# Motor_Control.net
KiCad netlist of a schematic drawn in Altium Designer
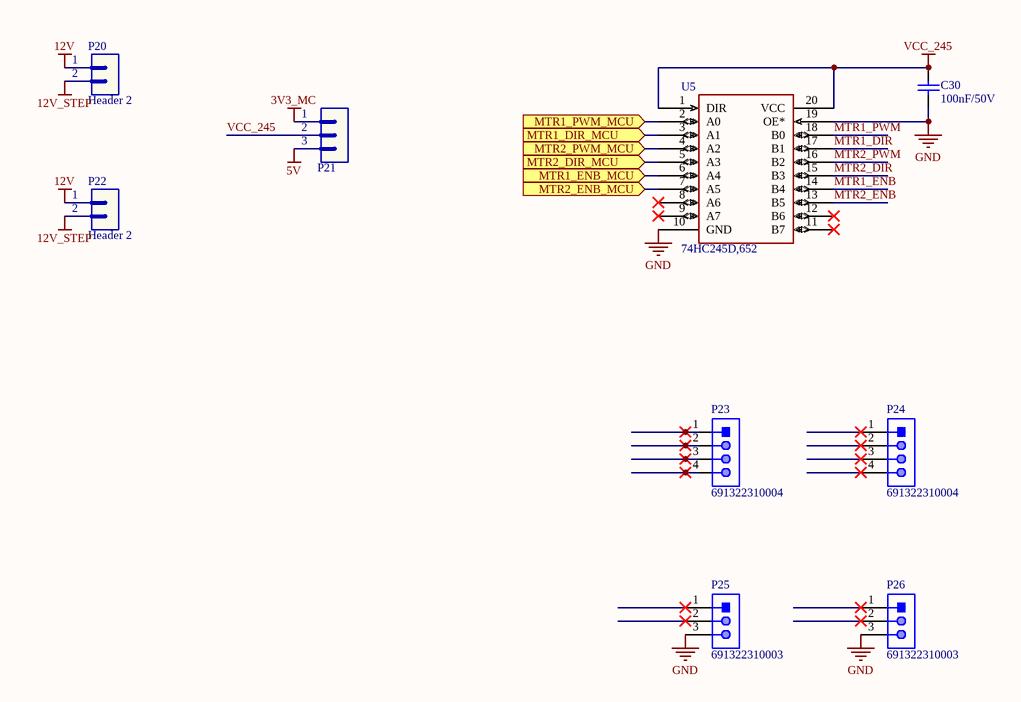
[diagram p0: Motor Control.SchDoc]

(export (version "E")
  (design (tool "Eeschema 10.0.6"))
  (components
    (comp (ref "C30")
      (value "100nF/50V")
      (footprint "CAP-SM-0805")
      (description "CAP CER 0.1UF 50V Y5V 0805")
      (fields
        (field (name "MANUFACTURER") "Samsung Electro-Mechanics")
        (field (name "MANUFACTURER PART NUMBER") "CL21F104ZBCNNNC")
      )
      (libsource (lib "Capacitor") (part "Cap-100nF-50V-0805"))
    )
    (comp (ref "P20")
      (value "Header 2")
      (footprint "JP2")
      (description "Header, 2-Pin")
      (fields (field (name "PUBLISHER") "Altium Limited"))
      (libsource (lib "PIF_C16_lib") (part "Header 2"))
    )
    (comp (ref "P21")
      (value "Header 3")
      (footprint "JP3")
      (description "Header, 3-Pin")
      (fields (field (name "PUBLISHER") "Altium Limited"))
      (libsource (lib "Header-Connector") (part "Header 3"))
    )
    (comp (ref "P22")
      (value "Header 2")
      (footprint "JP2")
      (description "Header, 2-Pin")
      (fields (field (name "PUBLISHER") "Altium Limited"))
      (libsource (lib "PIF_C16_lib") (part "Header 2"))
    )
    (comp (ref "P23")
      (value "691322310004")
      (footprint "691322310004")
      (description "WR-TBL Serie 322 Horizontal PCB Header, Pluggable, pitch 3.81mm, 4p")
      (fields (field (name "PUBLISHER") "Wurth Elektronik"))
      (libsource (lib "691322310002_Altium_WR-TBL_rev19a") (part "691322310004"))
    )
    (comp (ref "P24")
      (value "691322310004")
      (footprint "691322310004")
      (description "WR-TBL Serie 322 Horizontal PCB Header, Pluggable, pitch 3.81mm, 4p")
      (fields (field (name "PUBLISHER") "Wurth Elektronik"))
      (libsource (lib "691322310002_Altium_WR-TBL_rev19a") (part "691322310004"))
    )
    (comp (ref "P25")
      (value "691322310003")
      (footprint "691322310003")
      (description "WR-TBL Serie 322 Horizontal PCB Header, Pluggable, pitch 3.81mm, 3p")
      (fields (field (name "PUBLISHER") "Wurth Elektronik"))
      (libsource (lib "691322310002_Altium_WR-TBL_rev19a") (part "691322310003"))
    )
    (comp (ref "P26")
      (value "691322310003")
      (footprint "691322310003")
      (description "WR-TBL Serie 322 Horizontal PCB Header, Pluggable, pitch 3.81mm, 3p")
      (fields (field (name "PUBLISHER") "Wurth Elektronik"))
      (libsource (lib "691322310002_Altium_WR-TBL_rev19a") (part "691322310003"))
    )
    (comp (ref "U5")
      (value "74HC245D,652")
      (footprint "SOT163-1_NEX")
      (libsource (lib "PIF_robot") (part "74HC245D,652"))
    )
  )
  (nets
    (net (code "1") (name "/MTR1_DIR") (class "Default")
      (node (ref "U5") (pin "17") (pinfunction "B1_17") (pintype "bidirectional"))
    )
    (net (code "2") (name "/MTR1_DIR_MCU") (class "Default")
      (node (ref "U5") (pin "3") (pinfunction "A1_3") (pintype "bidirectional"))
    )
    (net (code "3") (name "/MTR1_ENB") (class "Default")
      (node (ref "U5") (pin "14") (pinfunction "B4_14") (pintype "bidirectional"))
    )
    (net (code "4") (name "/MTR1_ENB_MCU") (class "Default")
      (node (ref "U5") (pin "6") (pinfunction "A4_6") (pintype "bidirectional"))
    )
    (net (code "5") (name "/MTR1_PWM") (class "Default")
      (node (ref "U5") (pin "18") (pinfunction "B0_18") (pintype "bidirectional"))
    )
    (net (code "6") (name "/MTR1_PWM_MCU") (class "Default")
      (node (ref "U5") (pin "2") (pinfunction "A0_2") (pintype "bidirectional"))
    )
    (net (code "7") (name "/MTR2_DIR") (class "Default")
      (node (ref "U5") (pin "15") (pinfunction "B3_15") (pintype "bidirectional"))
    )
    (net (code "8") (name "/MTR2_DIR_MCU") (class "Default")
      (node (ref "U5") (pin "5") (pinfunction "A3_5") (pintype "bidirectional"))
    )
    (net (code "9") (name "/MTR2_ENB") (class "Default")
      (node (ref "U5") (pin "13") (pinfunction "B5_13") (pintype "bidirectional"))
    )
    (net (code "10") (name "/MTR2_ENB_MCU") (class "Default")
      (node (ref "U5") (pin "7") (pinfunction "A5_7") (pintype "bidirectional"))
    )
    (net (code "11") (name "/MTR2_PWM") (class "Default")
      (node (ref "U5") (pin "16") (pinfunction "B2_16") (pintype "bidirectional"))
    )
    (net (code "12") (name "/MTR2_PWM_MCU") (class "Default")
      (node (ref "U5") (pin "4") (pinfunction "A2_4") (pintype "bidirectional"))
    )
    (net (code "13") (name "3V3_MC") (class "Default")
      (node (ref "P21") (pin "1") (pinfunction "1_1") (pintype "passive"))
    )
    (net (code "14") (name "5V") (class "Default")
      (node (ref "P21") (pin "3") (pinfunction "3_3") (pintype "passive"))
    )
    (net (code "15") (name "12V") (class "Default")
      (node (ref "P20") (pin "1") (pinfunction "1_1") (pintype "passive"))
      (node (ref "P22") (pin "1") (pinfunction "1_1") (pintype "passive"))
    )
    (net (code "16") (name "12V_STEP") (class "Default")
      (node (ref "P20") (pin "2") (pinfunction "2_2") (pintype "passive"))
      (node (ref "P22") (pin "2") (pinfunction "2_2") (pintype "passive"))
    )
    (net (code "17") (name "GND") (class "Default")
      (node (ref "C30") (pin "1") (pinfunction "1_1") (pintype "passive"))
      (node (ref "P25") (pin "3") (pinfunction "3_3") (pintype "passive"))
      (node (ref "P26") (pin "3") (pinfunction "3_3") (pintype "passive"))
      (node (ref "U5") (pin "10") (pinfunction "GND_10") (pintype "power_in"))
      (node (ref "U5") (pin "19") (pinfunction "OE*_19") (pintype "input"))
    )
    (net (code "18") (name "VCC_245") (class "Default")
      (node (ref "C30") (pin "2") (pinfunction "2_2") (pintype "passive"))
      (node (ref "P21") (pin "2") (pinfunction "2_2") (pintype "passive"))
      (node (ref "U5") (pin "1") (pinfunction "DIR_1") (pintype "input"))
      (node (ref "U5") (pin "20") (pinfunction "VCC_20") (pintype "power_in"))
    )
    (net (code "19") (name "unconnected-(P23-Pad1)") (class "Default")
      (node (ref "P23") (pin "1") (pinfunction "1_1") (pintype "passive+no_connect"))
    )
    (net (code "20") (name "unconnected-(P23-Pad2)") (class "Default")
      (node (ref "P23") (pin "2") (pinfunction "2_2") (pintype "passive+no_connect"))
    )
    (net (code "21") (name "unconnected-(P23-Pad3)") (class "Default")
      (node (ref "P23") (pin "3") (pinfunction "3_3") (pintype "passive+no_connect"))
    )
    (net (code "22") (name "unconnected-(P23-Pad4)") (class "Default")
      (node (ref "P23") (pin "4") (pinfunction "4_4") (pintype "passive+no_connect"))
    )
    (net (code "23") (name "unconnected-(P24-Pad1)") (class "Default")
      (node (ref "P24") (pin "1") (pinfunction "1_1") (pintype "passive+no_connect"))
    )
    (net (code "24") (name "unconnected-(P24-Pad2)") (class "Default")
      (node (ref "P24") (pin "2") (pinfunction "2_2") (pintype "passive+no_connect"))
    )
    (net (code "25") (name "unconnected-(P24-Pad3)") (class "Default")
      (node (ref "P24") (pin "3") (pinfunction "3_3") (pintype "passive+no_connect"))
    )
    (net (code "26") (name "unconnected-(P24-Pad4)") (class "Default")
      (node (ref "P24") (pin "4") (pinfunction "4_4") (pintype "passive+no_connect"))
    )
    (net (code "27") (name "unconnected-(P25-Pad1)") (class "Default")
      (node (ref "P25") (pin "1") (pinfunction "1_1") (pintype "passive+no_connect"))
    )
    (net (code "28") (name "unconnected-(P25-Pad2)") (class "Default")
      (node (ref "P25") (pin "2") (pinfunction "2_2") (pintype "passive+no_connect"))
    )
    (net (code "29") (name "unconnected-(P26-Pad1)") (class "Default")
      (node (ref "P26") (pin "1") (pinfunction "1_1") (pintype "passive+no_connect"))
    )
    (net (code "30") (name "unconnected-(P26-Pad2)") (class "Default")
      (node (ref "P26") (pin "2") (pinfunction "2_2") (pintype "passive+no_connect"))
    )
    (net (code "31") (name "unconnected-(U5-A6-Pad8)") (class "Default")
      (node (ref "U5") (pin "8") (pinfunction "A6_8") (pintype "bidirectional+no_connect"))
    )
    (net (code "32") (name "unconnected-(U5-A7-Pad9)") (class "Default")
      (node (ref "U5") (pin "9") (pinfunction "A7_9") (pintype "bidirectional+no_connect"))
    )
    (net (code "33") (name "unconnected-(U5-B6-Pad12)") (class "Default")
      (node (ref "U5") (pin "12") (pinfunction "B6_12") (pintype "bidirectional+no_connect"))
    )
    (net (code "34") (name "unconnected-(U5-B7-Pad11)") (class "Default")
      (node (ref "U5") (pin "11") (pinfunction "B7_11") (pintype "bidirectional+no_connect"))
    )
  )
)
